# pcb-pick-plaz-hall_v1.net
KiCad netlist of a schematic drawn in EAGLE
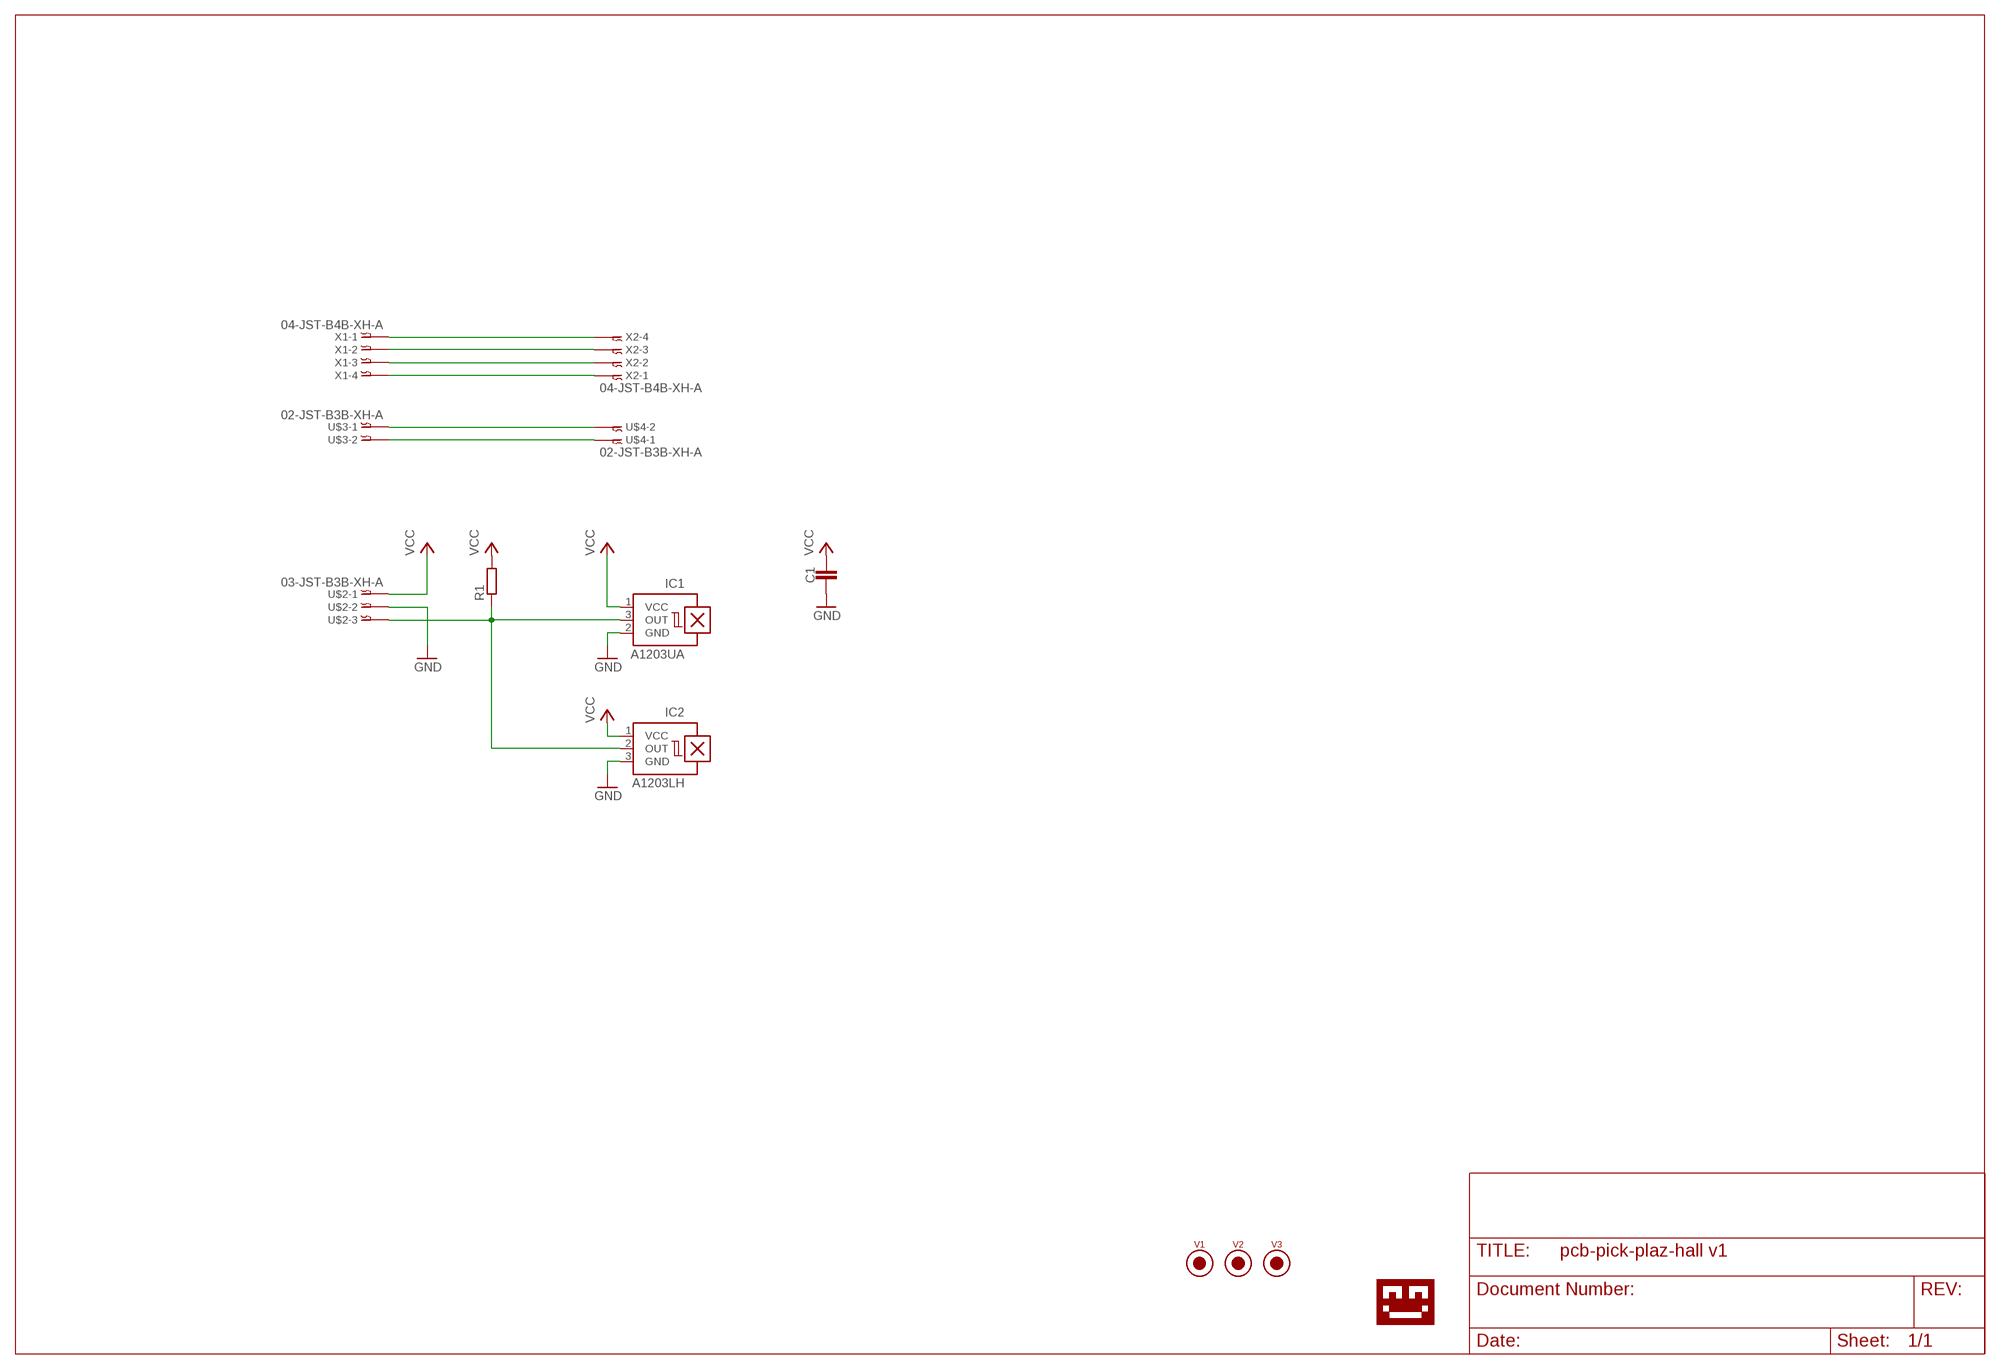
[diagram p0: schematic, sheet 1]

(export (version "E")
  (design (tool "Eeschema 10.0.6"))
  (components
    (comp (ref "C1")
      (value "CAPACITOR0603_CAP")
      (footprint "eagle-import:0603_CAP")
      (libsource (lib "eagle-import") (part "CAPACITOR0603_CAP"))
    )
    (comp (ref "IC1")
      (value "A1203UA")
      (footprint "eagle-import:SIP3-UA")
      (libsource (lib "eagle-import") (part "A12?UA03"))
    )
    (comp (ref "IC2")
      (value "A1203LH")
      (footprint "eagle-import:SOT23-W")
      (fields (field (name "MF") "ALLEGRO MICROSYSTEMS, INC.") (field (name "MPN") "A1203LLHLT-T"))
      (libsource (lib "eagle-import") (part "A12?LH03"))
    )
    (comp (ref "R1")
      (value "RESISTOR0603_RES")
      (footprint "eagle-import:0603-RES")
      (libsource (lib "eagle-import") (part "RESISTOR0603_RES"))
    )
    (comp (ref "U$1")
      (value "LOGO-TOBENG-1MM")
      (footprint "eagle-import:TOBENG-1MM")
      (libsource (lib "eagle-import") (part "LOGO-TOBENG-1MM"))
    )
    (comp (ref "U$2")
      (value "03-JST-B3B-XH-A")
      (footprint "eagle-import:B3B-XH")
      (libsource (lib "eagle-import") (part "03-JST-B3B-XH-A"))
    )
    (comp (ref "U$3")
      (value "02-JST-B3B-XH-A")
      (footprint "eagle-import:B2B-XH")
      (libsource (lib "eagle-import") (part "02-JST-B3B-XH-A"))
    )
    (comp (ref "U$4")
      (value "02-JST-B3B-XH-A")
      (footprint "eagle-import:B2B-XH")
      (libsource (lib "eagle-import") (part "02-JST-B3B-XH-A"))
    )
    (comp (ref "V1")
      (value "FIDUCIAL2MM")
      (footprint "eagle-import:FIDUCIAL_2MM")
      (libsource (lib "eagle-import") (part "FIDUCIAL2MM"))
    )
    (comp (ref "V2")
      (value "FIDUCIAL2MM")
      (footprint "eagle-import:FIDUCIAL_2MM")
      (libsource (lib "eagle-import") (part "FIDUCIAL2MM"))
    )
    (comp (ref "V3")
      (value "FIDUCIAL2MM")
      (footprint "eagle-import:FIDUCIAL_2MM")
      (libsource (lib "eagle-import") (part "FIDUCIAL2MM"))
    )
    (comp (ref "X1")
      (value "04-JST-B4B-XH-A")
      (footprint "eagle-import:B4B-XH")
      (libsource (lib "eagle-import") (part "04-JST-B4B-XH-A"))
    )
    (comp (ref "X2")
      (value "04-JST-B4B-XH-A")
      (footprint "eagle-import:B4B-XH")
      (libsource (lib "eagle-import") (part "04-JST-B4B-XH-A"))
    )
  )
  (nets
    (net (code "1") (name "GND") (class "Default")
      (node (ref "C1") (pin "2") (pinfunction "2_2") (pintype "bidirectional"))
      (node (ref "IC1") (pin "2") (pinfunction "GND_2") (pintype "power_in"))
      (node (ref "IC2") (pin "3") (pinfunction "GND_3") (pintype "power_in"))
      (node (ref "U$2") (pin "P$2") (pinfunction "1_P$2") (pintype "passive"))
    )
    (net (code "2") (name "Net-(IC1-OUT)") (class "Default")
      (node (ref "IC1") (pin "3") (pinfunction "OUT_3") (pintype "output"))
      (node (ref "IC2") (pin "2") (pinfunction "OUT_2") (pintype "output"))
      (node (ref "R1") (pin "1") (pinfunction "1_1") (pintype "passive"))
      (node (ref "U$2") (pin "P$3") (pinfunction "1_P$3") (pintype "passive"))
    )
    (net (code "3") (name "Net-(U$3A-1)") (class "Default")
      (node (ref "U$3") (pin "P$1") (pinfunction "1_P$1") (pintype "passive"))
      (node (ref "U$4") (pin "P$2") (pinfunction "1_P$2") (pintype "passive"))
    )
    (net (code "4") (name "Net-(U$3B-1)") (class "Default")
      (node (ref "U$3") (pin "P$2") (pinfunction "1_P$2") (pintype "passive"))
      (node (ref "U$4") (pin "P$1") (pinfunction "1_P$1") (pintype "passive"))
    )
    (net (code "5") (name "Net-(X1A-1)") (class "Default")
      (node (ref "X1") (pin "P$1") (pinfunction "1_P$1") (pintype "passive"))
      (node (ref "X2") (pin "P$4") (pinfunction "1_P$4") (pintype "passive"))
    )
    (net (code "6") (name "Net-(X1B-1)") (class "Default")
      (node (ref "X1") (pin "P$2") (pinfunction "1_P$2") (pintype "passive"))
      (node (ref "X2") (pin "P$3") (pinfunction "1_P$3") (pintype "passive"))
    )
    (net (code "7") (name "Net-(X1C-1)") (class "Default")
      (node (ref "X1") (pin "P$3") (pinfunction "1_P$3") (pintype "passive"))
      (node (ref "X2") (pin "P$2") (pinfunction "1_P$2") (pintype "passive"))
    )
    (net (code "8") (name "Net-(X1D-1)") (class "Default")
      (node (ref "X1") (pin "P$4") (pinfunction "1_P$4") (pintype "passive"))
      (node (ref "X2") (pin "P$1") (pinfunction "1_P$1") (pintype "passive"))
    )
    (net (code "9") (name "VCC") (class "Default")
      (node (ref "C1") (pin "1") (pinfunction "1_1") (pintype "bidirectional"))
      (node (ref "IC1") (pin "1") (pinfunction "VCC_1") (pintype "power_in"))
      (node (ref "IC2") (pin "1") (pinfunction "VCC_1") (pintype "power_in"))
      (node (ref "R1") (pin "2") (pinfunction "2_2") (pintype "passive"))
      (node (ref "U$2") (pin "P$1") (pinfunction "1_P$1") (pintype "passive"))
    )
  )
)
